# power.net
KiCad netlist of a schematic drawn in Altium Designer
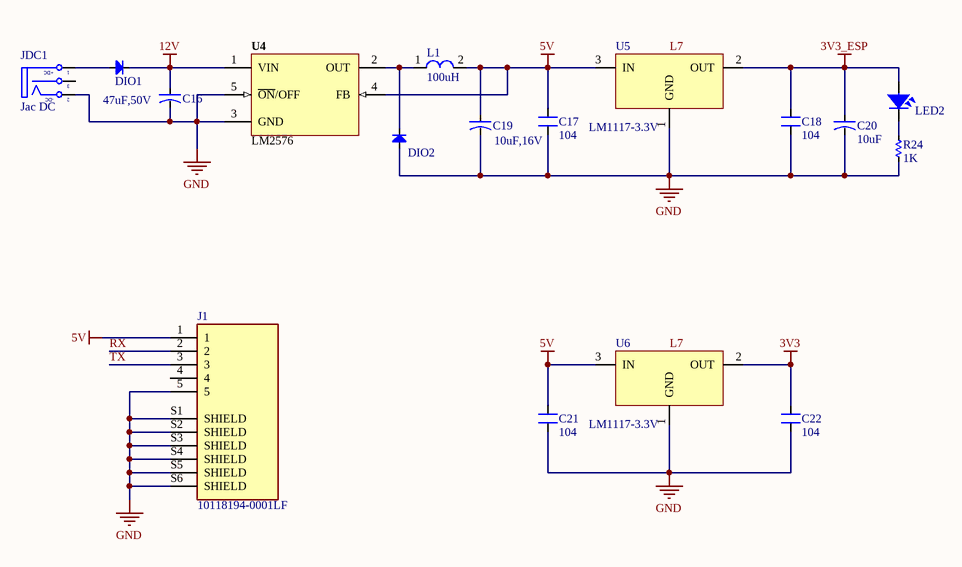
[diagram p0: power.SchDoc]

(export (version "E")
  (design (tool "Eeschema 10.0.6"))
  (components
    (comp (ref "C16")
      (value "47uF,50V")
      (footprint "CAP-ALU-SMD-6.3x7.7x2.2")
      (description "Polarized Capacitor (Axial)")
      (fields (field (name "PUBLISHER") "Altium Limited"))
      (libsource (lib "LIBTanCN") (part "CN-ALU-SMD"))
    )
    (comp (ref "C17")
      (value "104")
      (footprint "SM-CAP-0805")
      (fields (field (name "DESIGNED BY") "VanDungEvn"))
      (libsource (lib "electronicvn-library1") (part "CN"))
    )
    (comp (ref "C18")
      (value "104")
      (footprint "SM-CAP-0805")
      (fields (field (name "DESIGNED BY") "VanDungEvn"))
      (libsource (lib "electronicvn-library1") (part "CN"))
    )
    (comp (ref "C19")
      (value "10uF,16V")
      (footprint "CAP-ALU-SMD-6.3x7.7x2.2")
      (description "Polarized Capacitor (Axial)")
      (fields (field (name "PUBLISHER") "Altium Limited"))
      (libsource (lib "LIBTanCN") (part "CN-ALU-SMD"))
    )
    (comp (ref "C20")
      (value "10uF")
      (footprint "CAP-ALU-SMD-5x5.5x1.4")
      (description "Polarized Capacitor (Axial)")
      (fields (field (name "PUBLISHER") "Altium Limited"))
      (libsource (lib "LIBTanCN") (part "CN-ALU-SMD"))
    )
    (comp (ref "C21")
      (value "104")
      (footprint "SM-CAP-0805")
      (fields (field (name "DESIGNED BY") "VanDungEvn"))
      (libsource (lib "electronicvn-library1") (part "CN"))
    )
    (comp (ref "C22")
      (value "104")
      (footprint "SM-CAP-0805")
      (fields (field (name "DESIGNED BY") "VanDungEvn"))
      (libsource (lib "electronicvn-library1") (part "CN"))
    )
    (comp (ref "DIO1")
      (value "Diode SMD")
      (footprint "DIO-SMD-106")
      (description "Default Diode")
      (fields (field (name "PUBLISHER") "Altium Limited"))
      (libsource (lib "LIBRARY") (part "Diode SMD"))
    )
    (comp (ref "DIO2")
      (value "Diode SMD")
      (footprint "DIO-SMD-106")
      (description "Default Diode")
      (fields (field (name "PUBLISHER") "Altium Limited"))
      (libsource (lib "LIBRARY") (part "Diode SMD"))
    )
    (comp (ref "J1")
      (value "10118194-0001LF")
      (footprint "AMPHENOL_10118194-0001LF")
      (description "USB - micro B USB 2.0 Receptacle Connector 5 Position Surface Mount, Right Angle; Through Hole")
      (fields (field (name "MF") "Amphenol ICC"))
      (libsource (lib "10118194-0001LF") (part "10118194-0001LF"))
    )
    (comp (ref "JDC1")
      (value "Jac DC")
      (footprint "DC0")
      (description "Jac DC input")
      (libsource (lib "LIBRARY") (part "DCIN"))
    )
    (comp (ref "L1")
      (value "100uH")
      (footprint "L-SMD-M-12x10")
      (fields
        (field (name "PARTNO") "78477010")
        (field (name "MANUFACTURER") "Wurth Elektronik")
        (field (name "CREATED BY") "Baojun Chen")
      )
      (libsource (lib "LIBRARY") (part "L-SMD-1"))
    )
    (comp (ref "LED2") (value "LED") (footprint "LED-0805-Blue") (libsource (lib "LIBRARY") (part "LED SMD")))
    (comp (ref "R24")
      (value "1K")
      (footprint "RES-SMD-0805")
      (description "Resistor")
      (fields
        (field (name "MANUFACTURER") "Generic Components")
        (field (name "PUBLISHER") "Altium Hobart Technology Centre")
      )
      (libsource (lib "LIBRARY") (part "Res-SMD"))
    )
    (comp (ref "U4") (value "LM2576") (footprint "TO263") (libsource (lib "LIBRARY") (part "LM2576")))
    (comp (ref "U5")
      (value "LM1117-3.3V")
      (footprint "SOT223")
      (description "800mA Low-Dropout Linear Regulator")
      (fields (field (name "CREATOR") "Nguyen Ba Bien"))
      (libsource (lib "LIBRARY") (part "LM1117"))
    )
    (comp (ref "U6")
      (value "LM1117-3.3V")
      (footprint "SOT223")
      (description "800mA Low-Dropout Linear Regulator")
      (fields (field (name "CREATOR") "Nguyen Ba Bien"))
      (libsource (lib "LIBRARY") (part "LM1117"))
    )
  )
  (nets
    (net (code "2") (name "/RX") (class "Default")
      (node (ref "J1") (pin "2") (pinfunction "2_2") (pintype "passive"))
    )
    (net (code "3") (name "/TX") (class "Default")
      (node (ref "J1") (pin "3") (pinfunction "3_3") (pintype "passive"))
    )
    (net (code "4") (name "3V3") (class "Default")
      (node (ref "C22") (pin "2") (pinfunction "2_2") (pintype "passive"))
      (node (ref "U6") (pin "2") (pinfunction "OUT_2") (pintype "passive"))
    )
    (net (code "5") (name "3V3_ESP") (class "Default")
      (node (ref "C18") (pin "2") (pinfunction "2_2") (pintype "passive"))
      (node (ref "C20") (pin "1") (pinfunction "1_1") (pintype "passive"))
      (node (ref "LED2") (pin "1") (pinfunction "1_1") (pintype "passive"))
      (node (ref "U5") (pin "2") (pinfunction "OUT_2") (pintype "passive"))
    )
    (net (code "6") (name "5V") (class "Default")
      (node (ref "C17") (pin "2") (pinfunction "2_2") (pintype "passive"))
      (node (ref "C19") (pin "1") (pinfunction "1_1") (pintype "passive"))
      (node (ref "C21") (pin "2") (pinfunction "2_2") (pintype "passive"))
      (node (ref "J1") (pin "1") (pinfunction "1_1") (pintype "passive"))
      (node (ref "L1") (pin "2") (pinfunction "2_2") (pintype "passive"))
      (node (ref "U4") (pin "4") (pinfunction "FB_4") (pintype "input"))
      (node (ref "U5") (pin "3") (pinfunction "IN_3") (pintype "passive"))
      (node (ref "U6") (pin "3") (pinfunction "IN_3") (pintype "passive"))
    )
    (net (code "7") (name "12V") (class "Default")
      (node (ref "C16") (pin "1") (pinfunction "1_1") (pintype "passive"))
      (node (ref "DIO1") (pin "2") (pinfunction "K_2") (pintype "passive"))
      (node (ref "U4") (pin "1") (pinfunction "VIN_1") (pintype "power_in"))
    )
    (net (code "8") (name "GND") (class "Default")
      (node (ref "C16") (pin "2") (pinfunction "2_2") (pintype "passive"))
      (node (ref "C17") (pin "1") (pinfunction "1_1") (pintype "passive"))
      (node (ref "C18") (pin "1") (pinfunction "1_1") (pintype "passive"))
      (node (ref "C19") (pin "2") (pinfunction "2_2") (pintype "passive"))
      (node (ref "C20") (pin "2") (pinfunction "2_2") (pintype "passive"))
      (node (ref "C21") (pin "1") (pinfunction "1_1") (pintype "passive"))
      (node (ref "C22") (pin "1") (pinfunction "1_1") (pintype "passive"))
      (node (ref "DIO2") (pin "1") (pinfunction "A_1") (pintype "passive"))
      (node (ref "J1") (pin "5") (pinfunction "5_5") (pintype "passive"))
      (node (ref "J1") (pin "S1") (pinfunction "SHIELD_S1") (pintype "passive"))
      (node (ref "J1") (pin "S2") (pinfunction "SHIELD_S2") (pintype "passive"))
      (node (ref "J1") (pin "S3") (pinfunction "SHIELD_S3") (pintype "passive"))
      (node (ref "J1") (pin "S4") (pinfunction "SHIELD_S4") (pintype "passive"))
      (node (ref "J1") (pin "S5") (pinfunction "SHIELD_S5") (pintype "passive"))
      (node (ref "J1") (pin "S6") (pinfunction "SHIELD_S6") (pintype "passive"))
      (node (ref "JDC1") (pin "2") (pinfunction "TN_2") (pintype "passive"))
      (node (ref "R24") (pin "1") (pinfunction "1_1") (pintype "passive"))
      (node (ref "U4") (pin "3") (pinfunction "GND_3") (pintype "power_in"))
      (node (ref "U4") (pin "5") (pinfunction "~{ON}/OFF_5") (pintype "input"))
      (node (ref "U5") (pin "1") (pinfunction "GND_1") (pintype "passive"))
      (node (ref "U6") (pin "1") (pinfunction "GND_1") (pintype "passive"))
    )
    (net (code "9") (name "Net-(DIO1-A)") (class "Default")
      (node (ref "DIO1") (pin "1") (pinfunction "A_1") (pintype "passive"))
      (node (ref "JDC1") (pin "1") (pinfunction "T_1") (pintype "passive"))
    )
    (net (code "10") (name "Net-(DIO2-K)") (class "Default")
      (node (ref "DIO2") (pin "2") (pinfunction "K_2") (pintype "passive"))
      (node (ref "L1") (pin "1") (pinfunction "1_1") (pintype "passive"))
      (node (ref "U4") (pin "2") (pinfunction "OUT_2") (pintype "power_in"))
    )
    (net (code "11") (name "Net-(LED2-Pad2)") (class "Default")
      (node (ref "LED2") (pin "2") (pinfunction "2_2") (pintype "passive"))
      (node (ref "R24") (pin "2") (pinfunction "2_2") (pintype "passive"))
    )
    (net (code "12") (name "unconnected-(J1-Pad4)") (class "Default")
      (node (ref "J1") (pin "4") (pinfunction "4_4") (pintype "passive"))
    )
    (net (code "13") (name "unconnected-(JDC1-S-Pad3)") (class "Default")
      (node (ref "JDC1") (pin "3") (pinfunction "S_3") (pintype "power_in"))
    )
  )
)
